# Capacitors_Package.net
KiCad netlist of a schematic drawn in Altium Designer
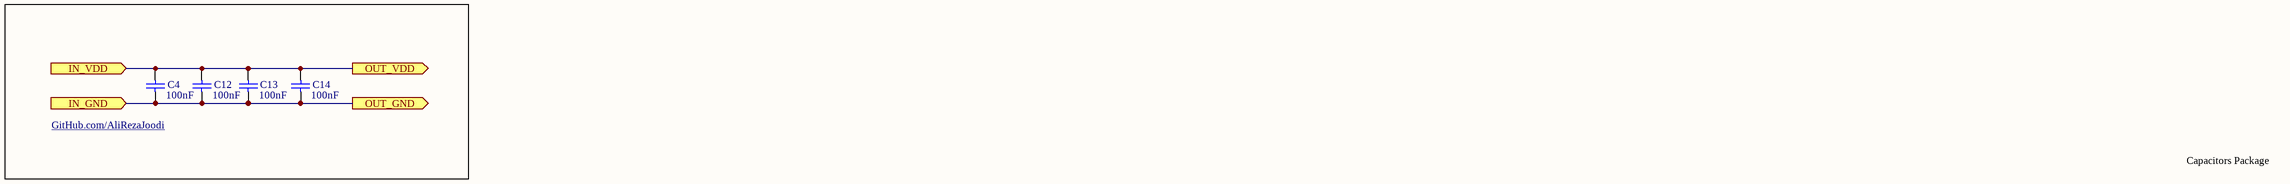
[diagram p0: Capacitors Package.SchDoc]

(export (version "E")
  (design (tool "Eeschema 10.0.6"))
  (components
    (comp (ref "C4")
      (value "100nF")
      (footprint "CAPNTO2.54-3.05x1.78A")
      (description "Capacitor")
      (fields (field (name "MANUFACTURER") "Generic Components") (field (name "PUBLISHER") "Altium Limited"))
      (libsource (lib "Miscellaneous Devices") (part "Cap"))
    )
    (comp (ref "C12")
      (value "100nF")
      (footprint "CAPNTO2.54-3.05x1.78A")
      (description "Capacitor")
      (fields (field (name "MANUFACTURER") "Generic Components") (field (name "PUBLISHER") "Altium Limited"))
      (libsource (lib "Miscellaneous Devices") (part "Cap"))
    )
    (comp (ref "C13")
      (value "100nF")
      (footprint "CAPNTO2.54-3.05x1.78A")
      (description "Capacitor")
      (fields (field (name "MANUFACTURER") "Generic Components") (field (name "PUBLISHER") "Altium Limited"))
      (libsource (lib "Miscellaneous Devices") (part "Cap"))
    )
    (comp (ref "C14")
      (value "100nF")
      (footprint "CAPNTO2.54-3.05x1.78A")
      (description "Capacitor")
      (fields (field (name "MANUFACTURER") "Generic Components") (field (name "PUBLISHER") "Altium Limited"))
      (libsource (lib "Miscellaneous Devices") (part "Cap"))
    )
  )
  (nets
    (net (code "1") (name "/IN_GND") (class "Default")
      (node (ref "C12") (pin "1") (pinfunction "1_1") (pintype "passive"))
      (node (ref "C13") (pin "1") (pinfunction "1_1") (pintype "passive"))
      (node (ref "C14") (pin "1") (pinfunction "1_1") (pintype "passive"))
      (node (ref "C4") (pin "1") (pinfunction "1_1") (pintype "passive"))
    )
    (net (code "2") (name "/IN_VDD") (class "Default")
      (node (ref "C12") (pin "2") (pinfunction "2_2") (pintype "passive"))
      (node (ref "C13") (pin "2") (pinfunction "2_2") (pintype "passive"))
      (node (ref "C14") (pin "2") (pinfunction "2_2") (pintype "passive"))
      (node (ref "C4") (pin "2") (pinfunction "2_2") (pintype "passive"))
    )
  )
)
